# STM32F7.net
KiCad netlist of a schematic drawn in Altium Designer
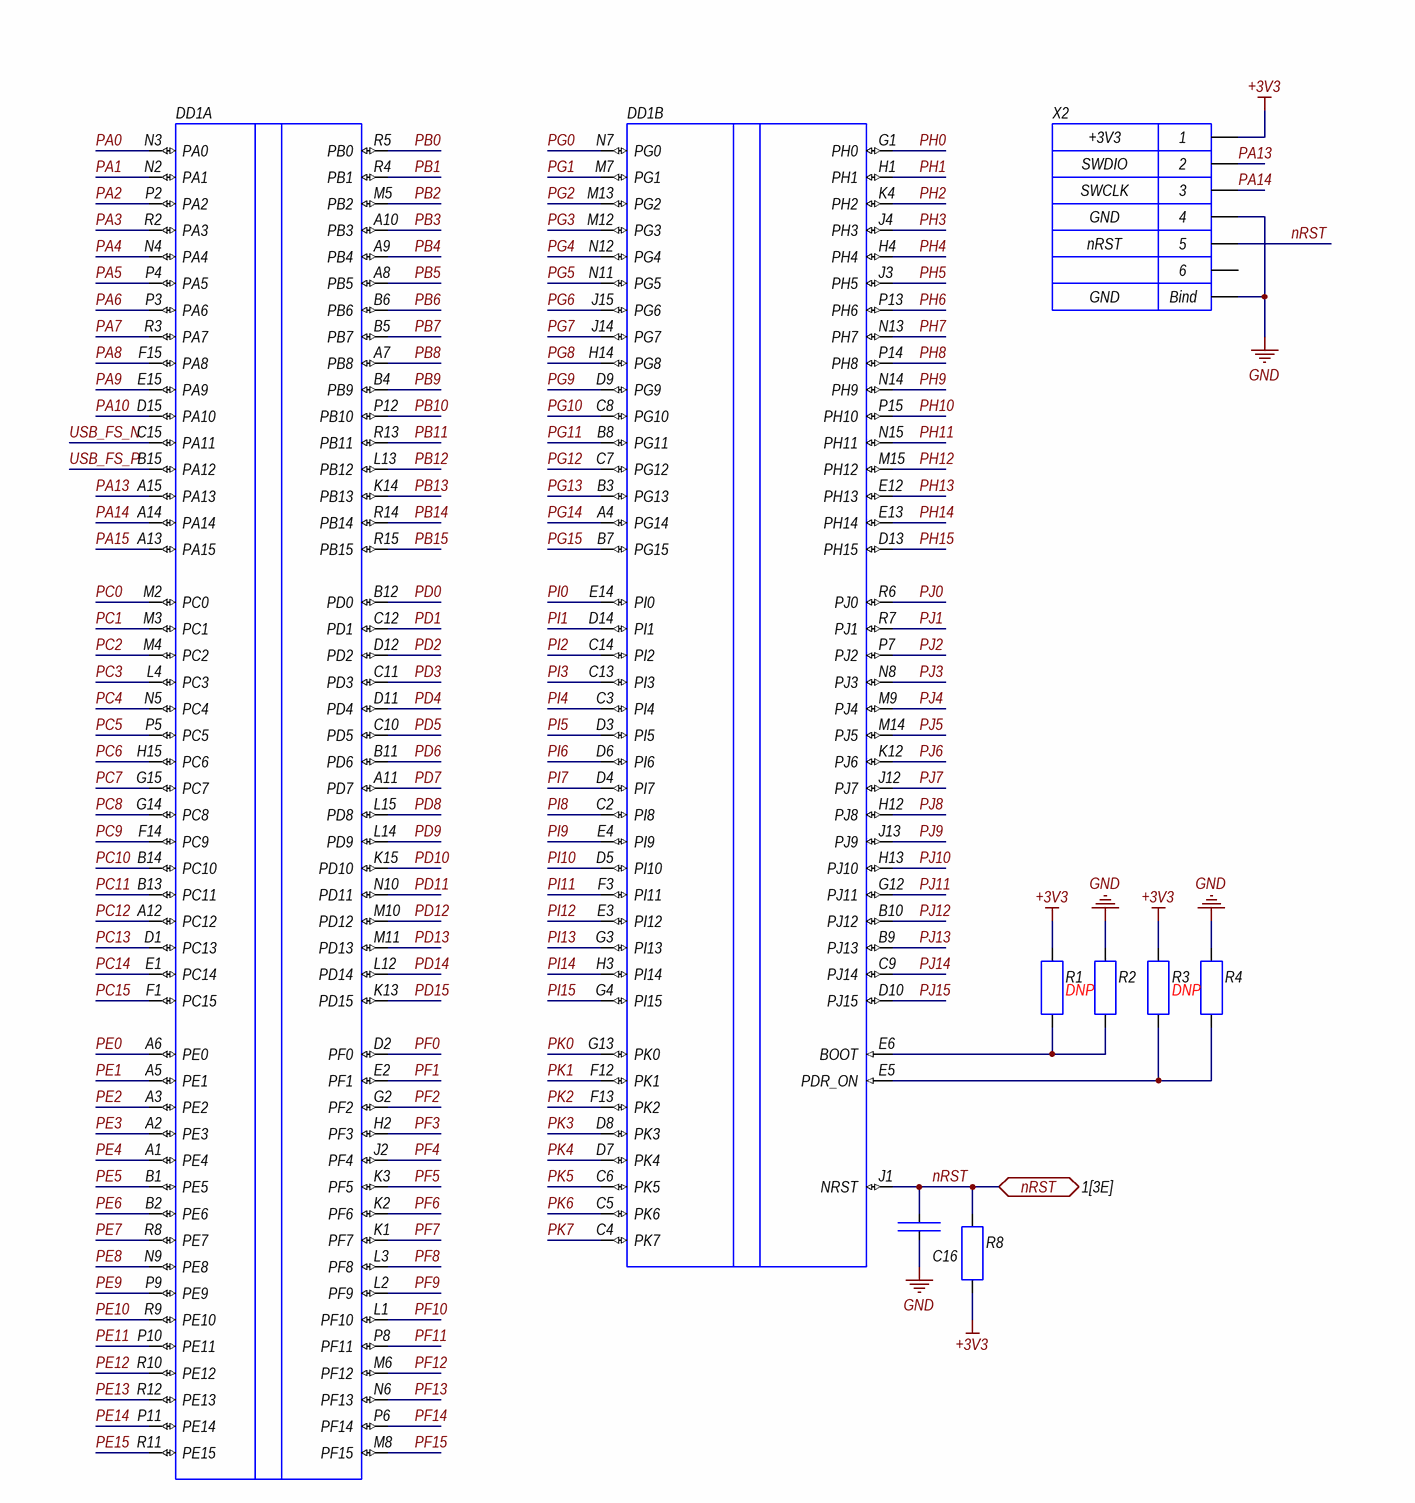
[diagram p0: STM32F7.SchDoc, top left]
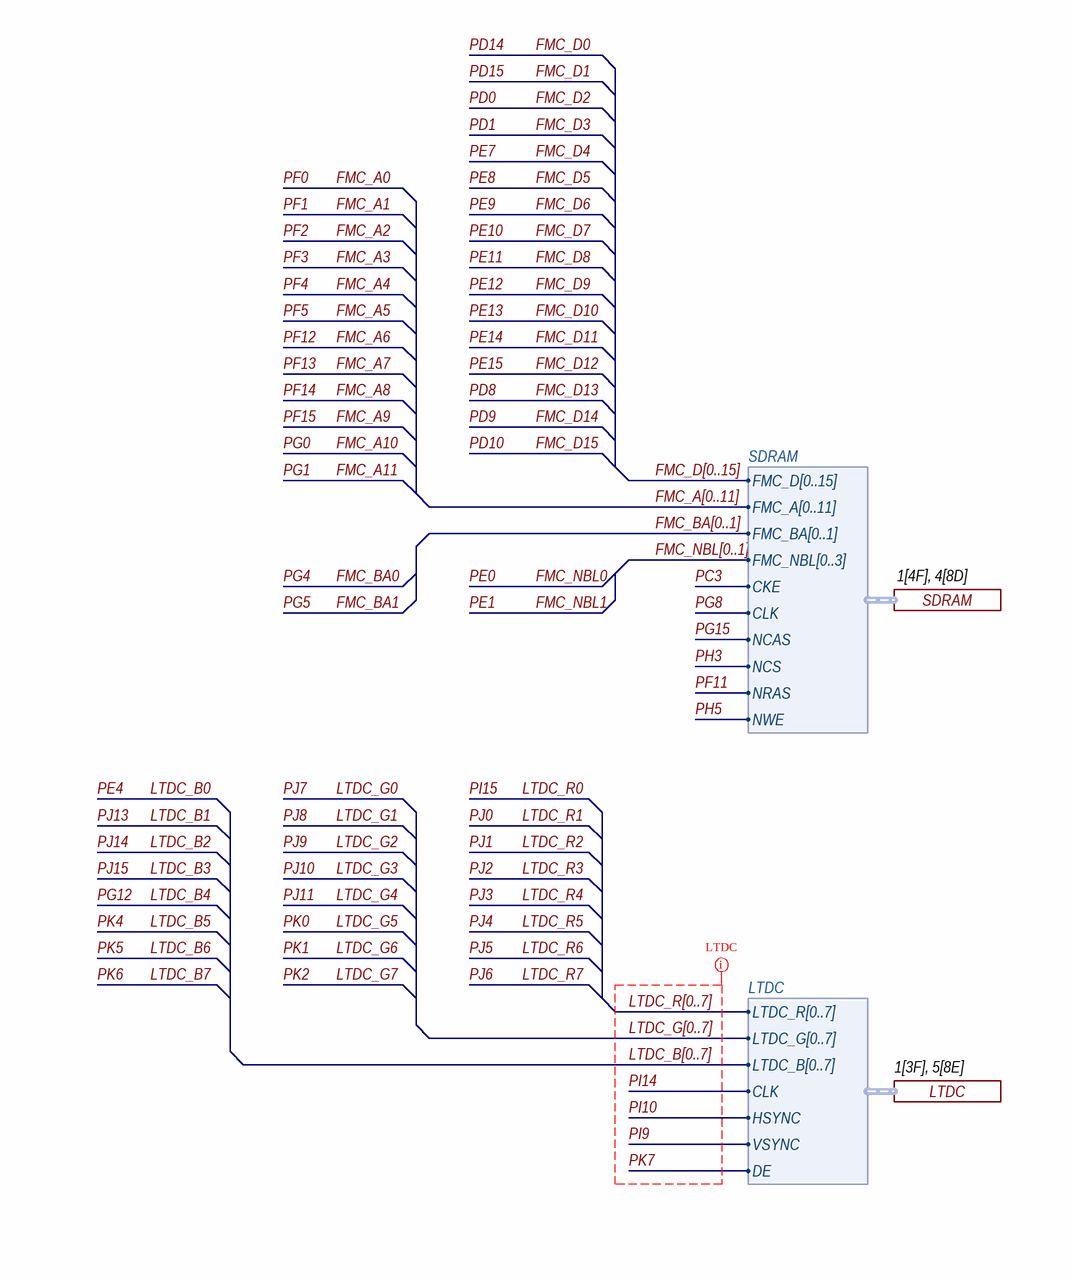
[diagram p1: STM32F7.SchDoc, top right]
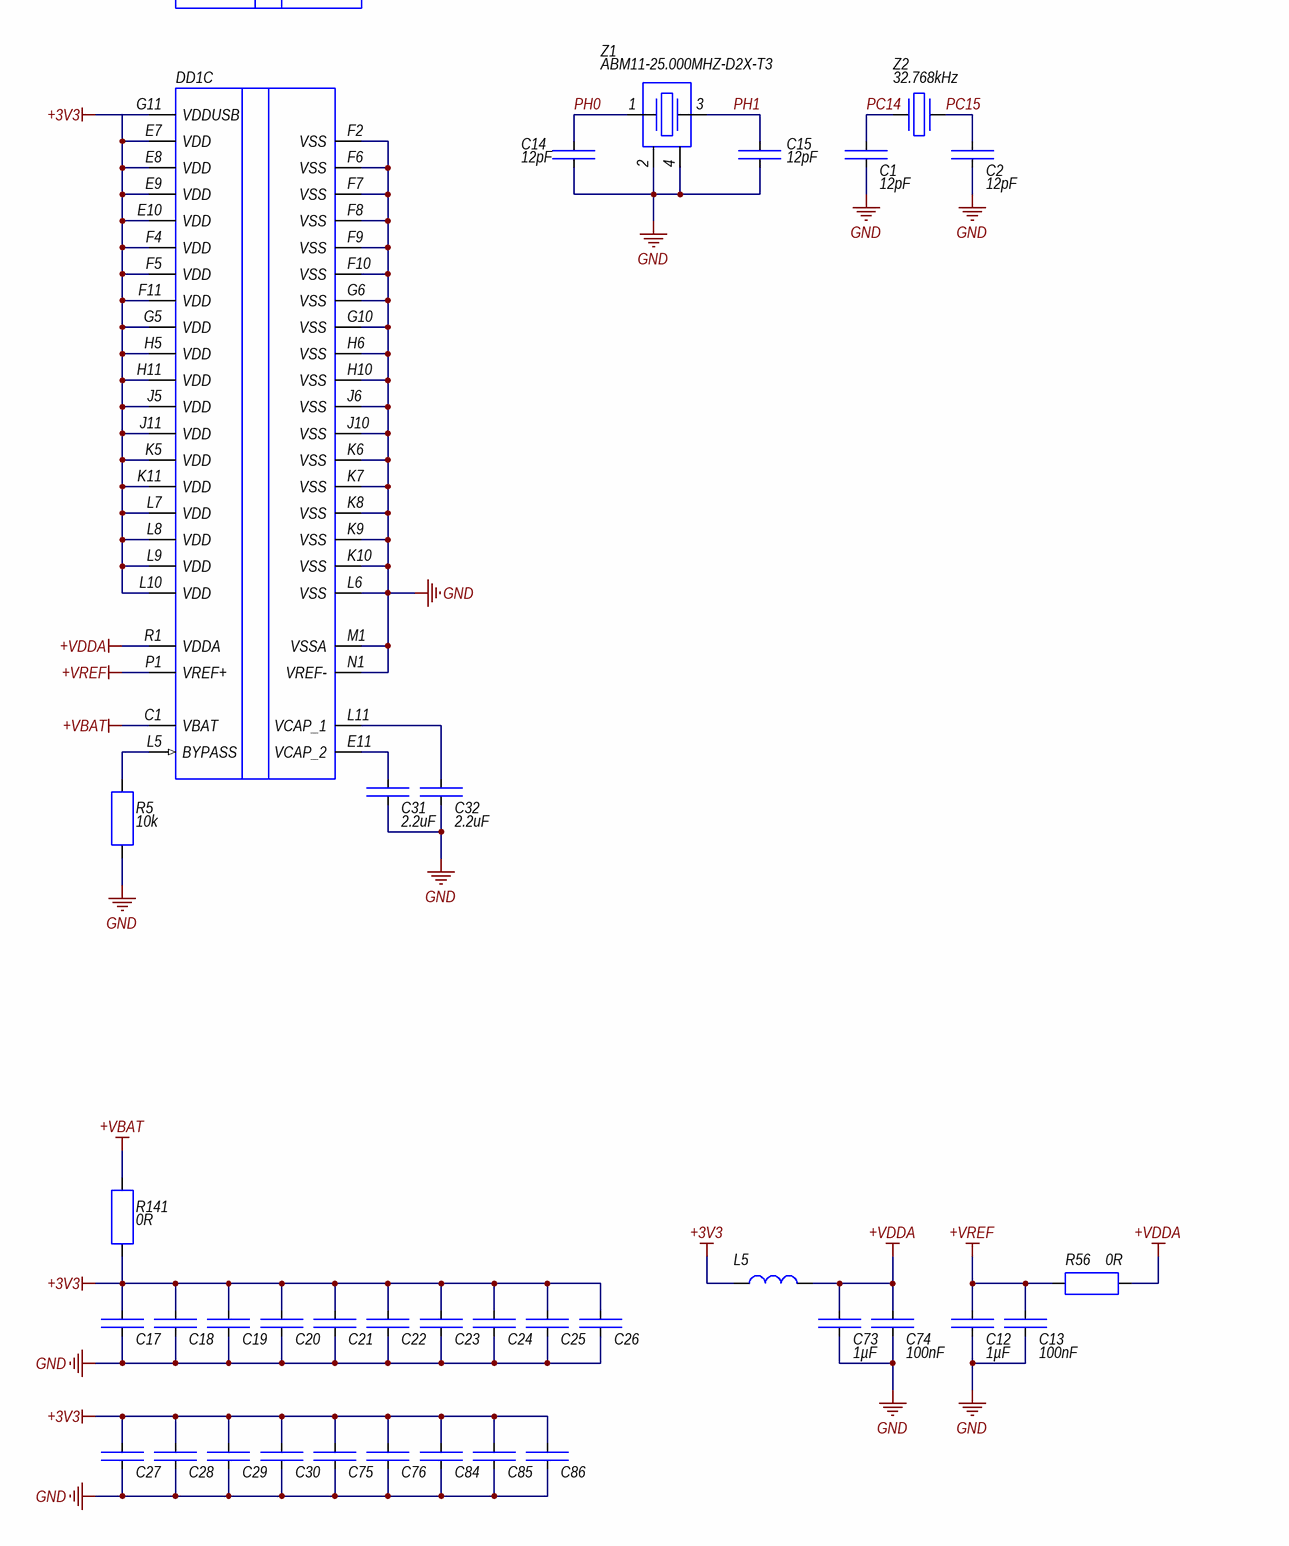
[diagram p2: STM32F7.SchDoc, bottom left]
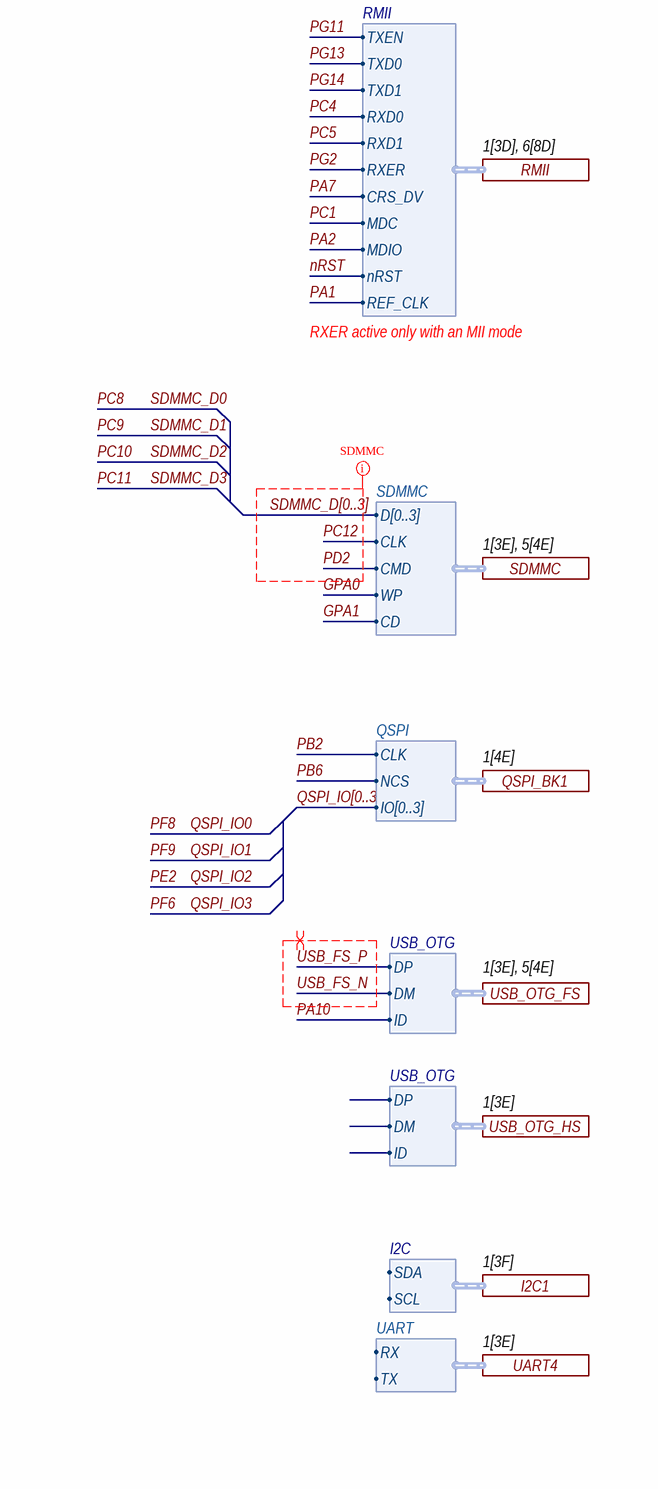
[diagram p3: STM32F7.SchDoc, bottom right]

(export (version "E")
  (design (tool "Eeschema 10.0.6"))
  (components
    (comp (ref "C1")
      (value "Конденсатор керам. ЧИП NP0, 5%, 0402, 12 пФ")
      (footprint "Capacitor 0402")
      (description "Cap Ceramic 12pF 50V C0G 2% Pad SMD 0402 125C Automotive T/R")
      (fields
        (field (name "CAPACITANCE") "12pF")
        (field (name "VOLTAGE") "50V")
        (field (name "MANUFACTURER") "Murata Manufacturing")
      )
      (libsource (lib "Eleps server") (part "Nonpolar Capacitor"))
    )
    (comp (ref "C2")
      (value "Конденсатор керам. ЧИП NP0, 5%, 0402, 12 пФ")
      (footprint "Capacitor 0402")
      (description "Cap Ceramic 12pF 50V C0G 2% Pad SMD 0402 125C Automotive T/R")
      (fields
        (field (name "CAPACITANCE") "12pF")
        (field (name "VOLTAGE") "50V")
        (field (name "MANUFACTURER") "Murata Manufacturing")
      )
      (libsource (lib "Eleps server") (part "Nonpolar Capacitor"))
    )
    (comp (ref "C12")
      (value "Конденсатор керам. ЧИП X5R, 10%, 0603, 1 мкФ")
      (footprint "Capacitor 0603")
      (description "Multilayer Ceramic Capacitors MLCC - SMD/SMT 0603 50V 1.0uF X5R 10%")
      (fields
        (field (name "CAPACITANCE") "1µF")
        (field (name "VOLTAGE") "50V")
        (field (name "MANUFACTURER") "Murata Electronics")
      )
      (libsource (lib "Eleps server") (part "Nonpolar Capacitor"))
    )
    (comp (ref "C13")
      (value "Конденсатор керам. ЧИП X7R, 10%, 0603, 0.1 мкФ")
      (footprint "Capacitor 0603")
      (fields
        (field (name "CAPACITANCE") "100nF")
        (field (name "VOLTAGE") "50V")
        (field (name "MANUFACTURER") "Yageo")
        (field (name "MANUFACTURER PART NUMBER") "CC0603KPX7R9BB104")
      )
      (libsource (lib "Eleps server") (part "Nonpolar Capacitor"))
    )
    (comp (ref "C14")
      (value "Конденсатор керам. ЧИП NP0, 5%, 0402, 12 пФ")
      (footprint "Capacitor 0402")
      (description "Cap Ceramic 12pF 50V C0G 2% Pad SMD 0402 125C Automotive T/R")
      (fields
        (field (name "CAPACITANCE") "12pF")
        (field (name "VOLTAGE") "50V")
        (field (name "MANUFACTURER") "Murata Manufacturing")
      )
      (libsource (lib "Eleps server") (part "Nonpolar Capacitor"))
    )
    (comp (ref "C15")
      (value "Конденсатор керам. ЧИП NP0, 5%, 0402, 12 пФ")
      (footprint "Capacitor 0402")
      (description "Cap Ceramic 12pF 50V C0G 2% Pad SMD 0402 125C Automotive T/R")
      (fields
        (field (name "CAPACITANCE") "12pF")
        (field (name "VOLTAGE") "50V")
        (field (name "MANUFACTURER") "Murata Manufacturing")
      )
      (libsource (lib "Eleps server") (part "Nonpolar Capacitor"))
    )
    (comp (ref "C16")
      (value "Конденсатор керам. ЧИП X5R, 10%, 0402, 0.1 мкФ")
      (footprint "Capacitor 0402")
      (description "Cap Ceramic 0.1uF 50V X5R 10% Pad SMD 0402 85C T/R")
      (fields (field (name "VOLTAGE") "50V") (field (name "MANUFACTURER") "Murata Manufacturing"))
      (libsource (lib "Eleps server") (part "Nonpolar Capacitor"))
    )
    (comp (ref "C17")
      (value "Конденсатор керам. ЧИП X5R, 10%, 0402, 0.1 мкФ")
      (footprint "Capacitor 0402")
      (description "Cap Ceramic 0.1uF 50V X5R 10% Pad SMD 0402 85C T/R")
      (fields (field (name "VOLTAGE") "50V") (field (name "MANUFACTURER") "Murata Manufacturing"))
      (libsource (lib "Eleps server") (part "Nonpolar Capacitor"))
    )
    (comp (ref "C18")
      (value "Конденсатор керам. ЧИП X5R, 10%, 0402, 0.1 мкФ")
      (footprint "Capacitor 0402")
      (description "Cap Ceramic 0.1uF 50V X5R 10% Pad SMD 0402 85C T/R")
      (fields (field (name "VOLTAGE") "50V") (field (name "MANUFACTURER") "Murata Manufacturing"))
      (libsource (lib "Eleps server") (part "Nonpolar Capacitor"))
    )
    (comp (ref "C19")
      (value "Конденсатор керам. ЧИП X5R, 10%, 0402, 0.1 мкФ")
      (footprint "Capacitor 0402")
      (description "Cap Ceramic 0.1uF 50V X5R 10% Pad SMD 0402 85C T/R")
      (fields (field (name "VOLTAGE") "50V") (field (name "MANUFACTURER") "Murata Manufacturing"))
      (libsource (lib "Eleps server") (part "Nonpolar Capacitor"))
    )
    (comp (ref "C20")
      (value "Конденсатор керам. ЧИП X5R, 10%, 0402, 0.1 мкФ")
      (footprint "Capacitor 0402")
      (description "Cap Ceramic 0.1uF 50V X5R 10% Pad SMD 0402 85C T/R")
      (fields (field (name "VOLTAGE") "50V") (field (name "MANUFACTURER") "Murata Manufacturing"))
      (libsource (lib "Eleps server") (part "Nonpolar Capacitor"))
    )
    (comp (ref "C21")
      (value "Конденсатор керам. ЧИП X5R, 10%, 0402, 0.1 мкФ")
      (footprint "Capacitor 0402")
      (description "Cap Ceramic 0.1uF 50V X5R 10% Pad SMD 0402 85C T/R")
      (fields (field (name "VOLTAGE") "50V") (field (name "MANUFACTURER") "Murata Manufacturing"))
      (libsource (lib "Eleps server") (part "Nonpolar Capacitor"))
    )
    (comp (ref "C22")
      (value "Конденсатор керам. ЧИП X5R, 10%, 0402, 0.1 мкФ")
      (footprint "Capacitor 0402")
      (description "Cap Ceramic 0.1uF 50V X5R 10% Pad SMD 0402 85C T/R")
      (fields (field (name "VOLTAGE") "50V") (field (name "MANUFACTURER") "Murata Manufacturing"))
      (libsource (lib "Eleps server") (part "Nonpolar Capacitor"))
    )
    (comp (ref "C23")
      (value "Конденсатор керам. ЧИП X5R, 10%, 0402, 0.1 мкФ")
      (footprint "Capacitor 0402")
      (description "Cap Ceramic 0.1uF 50V X5R 10% Pad SMD 0402 85C T/R")
      (fields (field (name "VOLTAGE") "50V") (field (name "MANUFACTURER") "Murata Manufacturing"))
      (libsource (lib "Eleps server") (part "Nonpolar Capacitor"))
    )
    (comp (ref "C24")
      (value "Конденсатор керам. ЧИП X5R, 10%, 0402, 0.1 мкФ")
      (footprint "Capacitor 0402")
      (description "Cap Ceramic 0.1uF 50V X5R 10% Pad SMD 0402 85C T/R")
      (fields (field (name "VOLTAGE") "50V") (field (name "MANUFACTURER") "Murata Manufacturing"))
      (libsource (lib "Eleps server") (part "Nonpolar Capacitor"))
    )
    (comp (ref "C25")
      (value "Конденсатор керам. ЧИП X5R, 10%, 0402, 0.1 мкФ")
      (footprint "Capacitor 0402")
      (description "Cap Ceramic 0.1uF 50V X5R 10% Pad SMD 0402 85C T/R")
      (fields (field (name "VOLTAGE") "50V") (field (name "MANUFACTURER") "Murata Manufacturing"))
      (libsource (lib "Eleps server") (part "Nonpolar Capacitor"))
    )
    (comp (ref "C26")
      (value "Конденсатор керам. ЧИП X5R, 10%, 0402, 0.1 мкФ")
      (footprint "Capacitor 0402")
      (description "Cap Ceramic 0.1uF 50V X5R 10% Pad SMD 0402 85C T/R")
      (fields (field (name "VOLTAGE") "50V") (field (name "MANUFACTURER") "Murata Manufacturing"))
      (libsource (lib "Eleps server") (part "Nonpolar Capacitor"))
    )
    (comp (ref "C27")
      (value "Конденсатор керам. ЧИП X5R, 10%, 0402, 0.1 мкФ")
      (footprint "Capacitor 0402")
      (description "Cap Ceramic 0.1uF 50V X5R 10% Pad SMD 0402 85C T/R")
      (fields (field (name "VOLTAGE") "50V") (field (name "MANUFACTURER") "Murata Manufacturing"))
      (libsource (lib "Eleps server") (part "Nonpolar Capacitor"))
    )
    (comp (ref "C28")
      (value "Конденсатор керам. ЧИП X5R, 10%, 0402, 0.1 мкФ")
      (footprint "Capacitor 0402")
      (description "Cap Ceramic 0.1uF 50V X5R 10% Pad SMD 0402 85C T/R")
      (fields (field (name "VOLTAGE") "50V") (field (name "MANUFACTURER") "Murata Manufacturing"))
      (libsource (lib "Eleps server") (part "Nonpolar Capacitor"))
    )
    (comp (ref "C29")
      (value "Конденсатор керам. ЧИП X5R, 10%, 0402, 0.1 мкФ")
      (footprint "Capacitor 0402")
      (description "Cap Ceramic 0.1uF 50V X5R 10% Pad SMD 0402 85C T/R")
      (fields (field (name "VOLTAGE") "50V") (field (name "MANUFACTURER") "Murata Manufacturing"))
      (libsource (lib "Eleps server") (part "Nonpolar Capacitor"))
    )
    (comp (ref "C30")
      (value "Конденсатор керам. ЧИП X5R, 10%, 0402, 0.1 мкФ")
      (footprint "Capacitor 0402")
      (description "Cap Ceramic 0.1uF 50V X5R 10% Pad SMD 0402 85C T/R")
      (fields (field (name "VOLTAGE") "50V") (field (name "MANUFACTURER") "Murata Manufacturing"))
      (libsource (lib "Eleps server") (part "Nonpolar Capacitor"))
    )
    (comp (ref "C31")
      (value "NCap")
      (footprint "SMD_1206")
      (fields (field (name "CAPACITANCE") "2.2uF") (field (name "PART NUMBER") "Capacitor_1206"))
      (libsource (lib "PhLib") (part "NCap"))
    )
    (comp (ref "C32")
      (value "NCap")
      (footprint "SMD_1206")
      (fields (field (name "CAPACITANCE") "2.2uF") (field (name "PART NUMBER") "Capacitor_1206"))
      (libsource (lib "PhLib") (part "NCap"))
    )
    (comp (ref "C73")
      (value "Конденсатор керам. ЧИП X5R, 10%, 0603, 1 мкФ")
      (footprint "Capacitor 0603")
      (description "Multilayer Ceramic Capacitors MLCC - SMD/SMT 0603 50V 1.0uF X5R 10%")
      (fields
        (field (name "CAPACITANCE") "1µF")
        (field (name "VOLTAGE") "50V")
        (field (name "MANUFACTURER") "Murata Electronics")
      )
      (libsource (lib "Eleps server") (part "Nonpolar Capacitor"))
    )
    (comp (ref "C74")
      (value "Конденсатор керам. ЧИП X7R, 10%, 0603, 0.1 мкФ")
      (footprint "Capacitor 0603")
      (fields
        (field (name "CAPACITANCE") "100nF")
        (field (name "VOLTAGE") "50V")
        (field (name "MANUFACTURER") "Yageo")
        (field (name "MANUFACTURER PART NUMBER") "CC0603KPX7R9BB104")
      )
      (libsource (lib "Eleps server") (part "Nonpolar Capacitor"))
    )
    (comp (ref "C75")
      (value "Конденсатор керам. ЧИП X5R, 10%, 0402, 0.1 мкФ")
      (footprint "Capacitor 0402")
      (description "Cap Ceramic 0.1uF 50V X5R 10% Pad SMD 0402 85C T/R")
      (fields (field (name "VOLTAGE") "50V") (field (name "MANUFACTURER") "Murata Manufacturing"))
      (libsource (lib "Eleps server") (part "Nonpolar Capacitor"))
    )
    (comp (ref "C76")
      (value "Конденсатор керам. ЧИП X5R, 10%, 0402, 0.1 мкФ")
      (footprint "Capacitor 0402")
      (description "Cap Ceramic 0.1uF 50V X5R 10% Pad SMD 0402 85C T/R")
      (fields (field (name "VOLTAGE") "50V") (field (name "MANUFACTURER") "Murata Manufacturing"))
      (libsource (lib "Eleps server") (part "Nonpolar Capacitor"))
    )
    (comp (ref "C84")
      (value "Конденсатор керам. ЧИП X5R, 10%, 0402, 0.1 мкФ")
      (footprint "Capacitor 0402")
      (description "Cap Ceramic 0.1uF 50V X5R 10% Pad SMD 0402 85C T/R")
      (fields (field (name "VOLTAGE") "50V") (field (name "MANUFACTURER") "Murata Manufacturing"))
      (libsource (lib "Eleps server") (part "Nonpolar Capacitor"))
    )
    (comp (ref "C85")
      (value "Конденсатор керам. ЧИП X5R, 10%, 0402, 0.1 мкФ")
      (footprint "Capacitor 0402")
      (description "Cap Ceramic 0.1uF 50V X5R 10% Pad SMD 0402 85C T/R")
      (fields (field (name "VOLTAGE") "50V") (field (name "MANUFACTURER") "Murata Manufacturing"))
      (libsource (lib "Eleps server") (part "Nonpolar Capacitor"))
    )
    (comp (ref "C86")
      (value "Конденсатор керам. ЧИП X5R, 10%, 0402, 0.1 мкФ")
      (footprint "Capacitor 0402")
      (description "Cap Ceramic 0.1uF 50V X5R 10% Pad SMD 0402 85C T/R")
      (fields (field (name "VOLTAGE") "50V") (field (name "MANUFACTURER") "Murata Manufacturing"))
      (libsource (lib "Eleps server") (part "Nonpolar Capacitor"))
    )
    (comp (ref "DD1")
      (value "Микросхема STM32F746NGH6")
      (footprint "STM-TFBGA216")
      (fields (field (name "PART NUMBER") "STM32F746NGH6") (field (name "MANUFACTURER") "STMicroelectronics"))
      (libsource (lib "PhLib") (part "STM32F746NGH6"))
    )
    (comp (ref "L5")
      (value "Дроссель BLM18HE152SN1D")
      (footprint "BLM18HE152SN1D")
      (description "Ferrite bead")
      (fields
        (field (name "MANUFACTURER") "Murata Electronics")
        (field (name "MANUFACTURER PART NUMBER") "BLM18HE152SN1D")
      )
      (libsource (lib "Eleps server") (part "Inductor"))
    )
    (comp (ref "R1")
      (value "~")
      (footprint "SMD_0402")
      (fields (field (name "PART NUMBER") "Resistor_0402"))
      (libsource (lib "PhLib") (part "Resistor"))
    )
    (comp (ref "R2")
      (value "~")
      (footprint "SMD_0402")
      (fields (field (name "PART NUMBER") "Resistor_0402"))
      (libsource (lib "PhLib") (part "Resistor"))
    )
    (comp (ref "R3")
      (value "~")
      (footprint "SMD_0402")
      (fields (field (name "PART NUMBER") "Resistor_0402"))
      (libsource (lib "PhLib") (part "Resistor"))
    )
    (comp (ref "R4")
      (value "~")
      (footprint "SMD_0402")
      (fields (field (name "PART NUMBER") "Resistor_0402"))
      (libsource (lib "PhLib") (part "Resistor"))
    )
    (comp (ref "R5")
      (value "~")
      (footprint "SMD_0402")
      (fields (field (name "PART NUMBER") "Resistor_0402") (field (name "RESISTANCE") "10k"))
      (libsource (lib "PhLib") (part "Resistor"))
    )
    (comp (ref "R8")
      (value "~")
      (footprint "SMD_0402")
      (fields (field (name "PART NUMBER") "Resistor_0402"))
      (libsource (lib "PhLib") (part "Resistor"))
    )
    (comp (ref "R56")
      (value "Resistor")
      (footprint "SMD_0402")
      (fields (field (name "DEVICE") "0R") (field (name "PART NUMBER") "Resistor_0402"))
      (libsource (lib "") (part "Resistor_1"))
    )
    (comp (ref "R141")
      (value "~")
      (footprint "SMD_0402")
      (fields (field (name "PART NUMBER") "Resistor_0402") (field (name "RESISTANCE") "0R"))
      (libsource (lib "PhLib") (part "Resistor"))
    )
    (comp (ref "X2")
      (value "Вилка DF13C-6P-1.25V(50)")
      (footprint "DF13C-6P-1.25V(50)")
      (fields (field (name "MANUFACTURER PART NUMBER") "DF13C-6P-1.25V(50)"))
      (libsource (lib "Eleps server") (part "6-connector-bind"))
    )
    (comp (ref "Z1")
      (value "Резонатор ABM11-25.000MHZ-D2X-T3")
      (footprint "ABM11-MFG")
      (description "Crystal 25MHz ±20ppm (Tol) ±20ppm (Stability) 10pF FUND 100Ohm 4-Pin Ultra Mini-CSMD T/R")
      (fields
        (field (name "MANUFACTURER") "Abracon")
        (field (name "MANUFACTURER PART NUMBER") "ABM11-25.000MHZ-D2X-T3")
      )
      (libsource (lib "Altium Vault") (part "KX-9A"))
    )
    (comp (ref "Z2")
      (value "Резонатор NX3215SA 32.768 кГц")
      (footprint "FP-NX3215SA-MFG")
      (description "32.768kHz")
      (fields
        (field (name "MANUFACTURER") "NDK")
        (field (name "MANUFACTURER PART NUMBER") "NX3215SA-32.768K-STD-MUA-8")
        (field (name "DEVICE") "32.768kHz")
      )
      (libsource (lib "Eleps server") (part "Resonator"))
    )
  )
  (nets
    (net (code "9") (name "+3V3") (class "Default")
      (node (ref "C17") (pin "1") (pinfunction "1_1") (pintype "passive"))
      (node (ref "C18") (pin "1") (pinfunction "1_1") (pintype "passive"))
      (node (ref "C19") (pin "1") (pinfunction "1_1") (pintype "passive"))
      (node (ref "C20") (pin "1") (pinfunction "1_1") (pintype "passive"))
      (node (ref "C21") (pin "1") (pinfunction "1_1") (pintype "passive"))
      (node (ref "C22") (pin "1") (pinfunction "1_1") (pintype "passive"))
      (node (ref "C23") (pin "1") (pinfunction "1_1") (pintype "passive"))
      (node (ref "C24") (pin "1") (pinfunction "1_1") (pintype "passive"))
      (node (ref "C25") (pin "1") (pinfunction "1_1") (pintype "passive"))
      (node (ref "C26") (pin "1") (pinfunction "1_1") (pintype "passive"))
      (node (ref "C27") (pin "1") (pinfunction "1_1") (pintype "passive"))
      (node (ref "C28") (pin "1") (pinfunction "1_1") (pintype "passive"))
      (node (ref "C29") (pin "1") (pinfunction "1_1") (pintype "passive"))
      (node (ref "C30") (pin "1") (pinfunction "1_1") (pintype "passive"))
      (node (ref "C75") (pin "1") (pinfunction "1_1") (pintype "passive"))
      (node (ref "C76") (pin "1") (pinfunction "1_1") (pintype "passive"))
      (node (ref "C84") (pin "1") (pinfunction "1_1") (pintype "passive"))
      (node (ref "C85") (pin "1") (pinfunction "1_1") (pintype "passive"))
      (node (ref "C86") (pin "1") (pinfunction "1_1") (pintype "passive"))
      (node (ref "DD1") (pin "E10") (pinfunction "VDD_E10") (pintype "power_in"))
      (node (ref "DD1") (pin "E7") (pinfunction "VDD_E7") (pintype "power_in"))
      (node (ref "DD1") (pin "E8") (pinfunction "VDD_E8") (pintype "power_in"))
      (node (ref "DD1") (pin "E9") (pinfunction "VDD_E9") (pintype "power_in"))
      (node (ref "DD1") (pin "F11") (pinfunction "VDD_F11") (pintype "power_in"))
      (node (ref "DD1") (pin "F4") (pinfunction "VDD_F4") (pintype "power_in"))
      (node (ref "DD1") (pin "F5") (pinfunction "VDD_F5") (pintype "power_in"))
      (node (ref "DD1") (pin "G11") (pinfunction "VDDUSB_G11") (pintype "power_in"))
      (node (ref "DD1") (pin "G5") (pinfunction "VDD_G5") (pintype "power_in"))
      (node (ref "DD1") (pin "H11") (pinfunction "VDD_H11") (pintype "power_in"))
      (node (ref "DD1") (pin "H5") (pinfunction "VDD_H5") (pintype "power_in"))
      (node (ref "DD1") (pin "J11") (pinfunction "VDD_J11") (pintype "power_in"))
      (node (ref "DD1") (pin "J5") (pinfunction "VDD_J5") (pintype "power_in"))
      (node (ref "DD1") (pin "K11") (pinfunction "VDD_K11") (pintype "power_in"))
      (node (ref "DD1") (pin "K5") (pinfunction "VDD_K5") (pintype "power_in"))
      (node (ref "DD1") (pin "L10") (pinfunction "VDD_L10") (pintype "power_in"))
      (node (ref "DD1") (pin "L7") (pinfunction "VDD_L7") (pintype "power_in"))
      (node (ref "DD1") (pin "L8") (pinfunction "VDD_L8") (pintype "power_in"))
      (node (ref "DD1") (pin "L9") (pinfunction "VDD_L9") (pintype "power_in"))
      (node (ref "L5") (pin "1") (pinfunction "1_1") (pintype "passive"))
      (node (ref "R1") (pin "2") (pinfunction "2_2") (pintype "passive"))
      (node (ref "R141") (pin "1") (pinfunction "1_1") (pintype "passive"))
      (node (ref "R3") (pin "2") (pinfunction "2_2") (pintype "passive"))
      (node (ref "R8") (pin "1") (pinfunction "1_1") (pintype "passive"))
      (node (ref "X2") (pin "1") (pinfunction "1_1") (pintype "passive"))
    )
    (net (code "10") (name "+VBAT") (class "Default")
      (node (ref "DD1") (pin "C1") (pinfunction "VBAT_C1") (pintype "power_in"))
      (node (ref "R141") (pin "2") (pinfunction "2_2") (pintype "passive"))
    )
    (net (code "11") (name "+VDDA") (class "Default")
      (node (ref "C73") (pin "1") (pinfunction "1_1") (pintype "passive"))
      (node (ref "C74") (pin "1") (pinfunction "1_1") (pintype "passive"))
      (node (ref "DD1") (pin "R1") (pinfunction "VDDA_R1") (pintype "power_in"))
      (node (ref "L5") (pin "2") (pinfunction "2_2") (pintype "passive"))
      (node (ref "R56") (pin "2") (pinfunction "2_2") (pintype "passive"))
    )
    (net (code "12") (name "+VREF") (class "Default")
      (node (ref "C12") (pin "1") (pinfunction "1_1") (pintype "passive"))
      (node (ref "C13") (pin "1") (pinfunction "1_1") (pintype "passive"))
      (node (ref "DD1") (pin "P1") (pinfunction "VREF+_P1") (pintype "power_in"))
      (node (ref "R56") (pin "1") (pinfunction "1_1") (pintype "passive"))
    )
    (net (code "13") (name "/FMC_A0") (class "Default")
      (node (ref "DD1") (pin "D2") (pinfunction "PF0_D2") (pintype "bidirectional"))
    )
    (net (code "14") (name "/FMC_A1") (class "Default")
      (node (ref "DD1") (pin "E2") (pinfunction "PF1_E2") (pintype "bidirectional"))
    )
    (net (code "15") (name "/FMC_A2") (class "Default")
      (node (ref "DD1") (pin "G2") (pinfunction "PF2_G2") (pintype "bidirectional"))
    )
    (net (code "16") (name "/FMC_A3") (class "Default")
      (node (ref "DD1") (pin "H2") (pinfunction "PF3_H2") (pintype "bidirectional"))
    )
    (net (code "17") (name "/FMC_A4") (class "Default")
      (node (ref "DD1") (pin "J2") (pinfunction "PF4_J2") (pintype "bidirectional"))
    )
    (net (code "18") (name "/FMC_A5") (class "Default")
      (node (ref "DD1") (pin "K3") (pinfunction "PF5_K3") (pintype "bidirectional"))
    )
    (net (code "19") (name "/FMC_A6") (class "Default")
      (node (ref "DD1") (pin "M6") (pinfunction "PF12_M6") (pintype "bidirectional"))
    )
    (net (code "20") (name "/FMC_A7") (class "Default")
      (node (ref "DD1") (pin "N6") (pinfunction "PF13_N6") (pintype "bidirectional"))
    )
    (net (code "21") (name "/FMC_A8") (class "Default")
      (node (ref "DD1") (pin "P6") (pinfunction "PF14_P6") (pintype "bidirectional"))
    )
    (net (code "22") (name "/FMC_A9") (class "Default")
      (node (ref "DD1") (pin "M8") (pinfunction "PF15_M8") (pintype "bidirectional"))
    )
    (net (code "23") (name "/FMC_A10") (class "Default")
      (node (ref "DD1") (pin "N7") (pinfunction "PG0_N7") (pintype "bidirectional"))
    )
    (net (code "24") (name "/FMC_A11") (class "Default")
      (node (ref "DD1") (pin "M7") (pinfunction "PG1_M7") (pintype "bidirectional"))
    )
    (net (code "26") (name "/FMC_BA0") (class "Default")
      (node (ref "DD1") (pin "N12") (pinfunction "PG4_N12") (pintype "bidirectional"))
    )
    (net (code "27") (name "/FMC_BA1") (class "Default")
      (node (ref "DD1") (pin "N11") (pinfunction "PG5_N11") (pintype "bidirectional"))
    )
    (net (code "29") (name "/FMC_D0") (class "Default")
      (node (ref "DD1") (pin "L12") (pinfunction "PD14_L12") (pintype "bidirectional"))
    )
    (net (code "30") (name "/FMC_D1") (class "Default")
      (node (ref "DD1") (pin "K13") (pinfunction "PD15_K13") (pintype "bidirectional"))
    )
    (net (code "31") (name "/FMC_D2") (class "Default")
      (node (ref "DD1") (pin "B12") (pinfunction "PD0_B12") (pintype "bidirectional"))
    )
    (net (code "32") (name "/FMC_D3") (class "Default")
      (node (ref "DD1") (pin "C12") (pinfunction "PD1_C12") (pintype "bidirectional"))
    )
    (net (code "33") (name "/FMC_D4") (class "Default")
      (node (ref "DD1") (pin "R8") (pinfunction "PE7_R8") (pintype "bidirectional"))
    )
    (net (code "34") (name "/FMC_D5") (class "Default")
      (node (ref "DD1") (pin "N9") (pinfunction "PE8_N9") (pintype "bidirectional"))
    )
    (net (code "35") (name "/FMC_D6") (class "Default")
      (node (ref "DD1") (pin "P9") (pinfunction "PE9_P9") (pintype "bidirectional"))
    )
    (net (code "36") (name "/FMC_D7") (class "Default")
      (node (ref "DD1") (pin "R9") (pinfunction "PE10_R9") (pintype "bidirectional"))
    )
    (net (code "37") (name "/FMC_D8") (class "Default")
      (node (ref "DD1") (pin "P10") (pinfunction "PE11_P10") (pintype "bidirectional"))
    )
    (net (code "38") (name "/FMC_D9") (class "Default")
      (node (ref "DD1") (pin "R10") (pinfunction "PE12_R10") (pintype "bidirectional"))
    )
    (net (code "39") (name "/FMC_D10") (class "Default")
      (node (ref "DD1") (pin "R12") (pinfunction "PE13_R12") (pintype "bidirectional"))
    )
    (net (code "40") (name "/FMC_D11") (class "Default")
      (node (ref "DD1") (pin "P11") (pinfunction "PE14_P11") (pintype "bidirectional"))
    )
    (net (code "41") (name "/FMC_D12") (class "Default")
      (node (ref "DD1") (pin "R11") (pinfunction "PE15_R11") (pintype "bidirectional"))
    )
    (net (code "42") (name "/FMC_D13") (class "Default")
      (node (ref "DD1") (pin "L15") (pinfunction "PD8_L15") (pintype "bidirectional"))
    )
    (net (code "43") (name "/FMC_D14") (class "Default")
      (node (ref "DD1") (pin "L14") (pinfunction "PD9_L14") (pintype "bidirectional"))
    )
    (net (code "44") (name "/FMC_D15") (class "Default")
      (node (ref "DD1") (pin "K15") (pinfunction "PD10_K15") (pintype "bidirectional"))
    )
    (net (code "46") (name "/FMC_NBL0") (class "Default")
      (node (ref "DD1") (pin "A6") (pinfunction "PE0_A6") (pintype "bidirectional"))
    )
    (net (code "47") (name "/FMC_NBL1") (class "Default")
      (node (ref "DD1") (pin "A5") (pinfunction "PE1_A5") (pintype "bidirectional"))
    )
    (net (code "51") (name "/LTDC_B0") (class "Default")
      (node (ref "DD1") (pin "A1") (pinfunction "PE4_A1") (pintype "bidirectional"))
    )
    (net (code "52") (name "/LTDC_B1") (class "Default")
      (node (ref "DD1") (pin "B9") (pinfunction "PJ13_B9") (pintype "bidirectional"))
    )
    (net (code "53") (name "/LTDC_B2") (class "Default")
      (node (ref "DD1") (pin "C9") (pinfunction "PJ14_C9") (pintype "bidirectional"))
    )
    (net (code "54") (name "/LTDC_B3") (class "Default")
      (node (ref "DD1") (pin "D10") (pinfunction "PJ15_D10") (pintype "bidirectional"))
    )
    (net (code "55") (name "/LTDC_B4") (class "Default")
      (node (ref "DD1") (pin "C7") (pinfunction "PG12_C7") (pintype "bidirectional"))
    )
    (net (code "56") (name "/LTDC_B5") (class "Default")
      (node (ref "DD1") (pin "D7") (pinfunction "PK4_D7") (pintype "bidirectional"))
    )
    (net (code "57") (name "/LTDC_B6") (class "Default")
      (node (ref "DD1") (pin "C6") (pinfunction "PK5_C6") (pintype "bidirectional"))
    )
    (net (code "58") (name "/LTDC_B7") (class "Default")
      (node (ref "DD1") (pin "C5") (pinfunction "PK6_C5") (pintype "bidirectional"))
    )
    (net (code "60") (name "/LTDC_G0") (class "Default")
      (node (ref "DD1") (pin "J12") (pinfunction "PJ7_J12") (pintype "bidirectional"))
    )
    (net (code "61") (name "/LTDC_G1") (class "Default")
      (node (ref "DD1") (pin "H12") (pinfunction "PJ8_H12") (pintype "bidirectional"))
    )
    (net (code "62") (name "/LTDC_G2") (class "Default")
      (node (ref "DD1") (pin "J13") (pinfunction "PJ9_J13") (pintype "bidirectional"))
    )
    (net (code "63") (name "/LTDC_G3") (class "Default")
      (node (ref "DD1") (pin "H13") (pinfunction "PJ10_H13") (pintype "bidirectional"))
    )
    (net (code "64") (name "/LTDC_G4") (class "Default")
      (node (ref "DD1") (pin "G12") (pinfunction "PJ11_G12") (pintype "bidirectional"))
    )
    (net (code "65") (name "/LTDC_G5") (class "Default")
      (node (ref "DD1") (pin "G13") (pinfunction "PK0_G13") (pintype "bidirectional"))
    )
    (net (code "66") (name "/LTDC_G6") (class "Default")
      (node (ref "DD1") (pin "F12") (pinfunction "PK1_F12") (pintype "bidirectional"))
    )
    (net (code "67") (name "/LTDC_G7") (class "Default")
      (node (ref "DD1") (pin "F13") (pinfunction "PK2_F13") (pintype "bidirectional"))
    )
    (net (code "69") (name "/LTDC_R0") (class "Default")
      (node (ref "DD1") (pin "G4") (pinfunction "PI15_G4") (pintype "bidirectional"))
    )
    (net (code "70") (name "/LTDC_R1") (class "Default")
      (node (ref "DD1") (pin "R6") (pinfunction "PJ0_R6") (pintype "bidirectional"))
    )
    (net (code "71") (name "/LTDC_R2") (class "Default")
      (node (ref "DD1") (pin "R7") (pinfunction "PJ1_R7") (pintype "bidirectional"))
    )
    (net (code "72") (name "/LTDC_R3") (class "Default")
      (node (ref "DD1") (pin "P7") (pinfunction "PJ2_P7") (pintype "bidirectional"))
    )
    (net (code "73") (name "/LTDC_R4") (class "Default")
      (node (ref "DD1") (pin "N8") (pinfunction "PJ3_N8") (pintype "bidirectional"))
    )
    (net (code "74") (name "/LTDC_R5") (class "Default")
      (node (ref "DD1") (pin "M9") (pinfunction "PJ4_M9") (pintype "bidirectional"))
    )
    (net (code "75") (name "/LTDC_R6") (class "Default")
      (node (ref "DD1") (pin "M14") (pinfunction "PJ5_M14") (pintype "bidirectional"))
    )
    (net (code "76") (name "/LTDC_R7") (class "Default")
      (node (ref "DD1") (pin "K12") (pinfunction "PJ6_K12") (pintype "bidirectional"))
    )
    (net (code "78") (name "/PA0") (class "Default")
      (node (ref "DD1") (pin "N3") (pinfunction "PA0_N3") (pintype "bidirectional"))
    )
    (net (code "79") (name "/PA1") (class "Default")
      (node (ref "DD1") (pin "N2") (pinfunction "PA1_N2") (pintype "bidirectional"))
    )
    (net (code "80") (name "/PA2") (class "Default")
      (node (ref "DD1") (pin "P2") (pinfunction "PA2_P2") (pintype "bidirectional"))
    )
    (net (code "81") (name "/PA3") (class "Default")
      (node (ref "DD1") (pin "R2") (pinfunction "PA3_R2") (pintype "bidirectional"))
    )
    (net (code "82") (name "/PA4") (class "Default")
      (node (ref "DD1") (pin "N4") (pinfunction "PA4_N4") (pintype "bidirectional"))
    )
    (net (code "83") (name "/PA5") (class "Default")
      (node (ref "DD1") (pin "P4") (pinfunction "PA5_P4") (pintype "bidirectional"))
    )
    (net (code "84") (name "/PA6") (class "Default")
      (node (ref "DD1") (pin "P3") (pinfunction "PA6_P3") (pintype "bidirectional"))
    )
    (net (code "85") (name "/PA7") (class "Default")
      (node (ref "DD1") (pin "R3") (pinfunction "PA7_R3") (pintype "bidirectional"))
    )
    (net (code "86") (name "/PA8") (class "Default")
      (node (ref "DD1") (pin "F15") (pinfunction "PA8_F15") (pintype "bidirectional"))
    )
    (net (code "87") (name "/PA9") (class "Default")
      (node (ref "DD1") (pin "E15") (pinfunction "PA9_E15") (pintype "bidirectional"))
    )
    (net (code "88") (name "/PA10") (class "Default")
      (node (ref "DD1") (pin "D15") (pinfunction "PA10_D15") (pintype "bidirectional"))
    )
    (net (code "89") (name "/PA13") (class "Default")
      (node (ref "DD1") (pin "A15") (pinfunction "PA13_A15") (pintype "bidirectional"))
      (node (ref "X2") (pin "2") (pinfunction "2_2") (pintype "passive"))
    )
    (net (code "90") (name "/PA14") (class "Default")
      (node (ref "DD1") (pin "A14") (pinfunction "PA14_A14") (pintype "bidirectional"))
      (node (ref "X2") (pin "3") (pinfunction "3_3") (pintype "passive"))
    )
    (net (code "91") (name "/PA15") (class "Default")
      (node (ref "DD1") (pin "A13") (pinfunction "PA15_A13") (pintype "bidirectional"))
    )
    (net (code "92") (name "/PB0") (class "Default")
      (node (ref "DD1") (pin "R5") (pinfunction "PB0_R5") (pintype "bidirectional"))
    )
    (net (code "93") (name "/PB1") (class "Default")
      (node (ref "DD1") (pin "R4") (pinfunction "PB1_R4") (pintype "bidirectional"))
    )
    (net (code "94") (name "/PB2") (class "Default")
      (node (ref "DD1") (pin "M5") (pinfunction "PB2_M5") (pintype "bidirectional"))
    )
    (net (code "95") (name "/PB3") (class "Default")
      (node (ref "DD1") (pin "A10") (pinfunction "PB3_A10") (pintype "bidirectional"))
    )
    (net (code "96") (name "/PB4") (class "Default")
      (node (ref "DD1") (pin "A9") (pinfunction "PB4_A9") (pintype "bidirectional"))
    )
    (net (code "97") (name "/PB5") (class "Default")
      (node (ref "DD1") (pin "A8") (pinfunction "PB5_A8") (pintype "bidirectional"))
    )
    (net (code "98") (name "/PB6") (class "Default")
      (node (ref "DD1") (pin "B6") (pinfunction "PB6_B6") (pintype "bidirectional"))
    )
    (net (code "99") (name "/PB7") (class "Default")
      (node (ref "DD1") (pin "B5") (pinfunction "PB7_B5") (pintype "bidirectional"))
    )
    (net (code "100") (name "/PB8") (class "Default")
      (node (ref "DD1") (pin "A7") (pinfunction "PB8_A7") (pintype "bidirectional"))
    )
    (net (code "101") (name "/PB9") (class "Default")
      (node (ref "DD1") (pin "B4") (pinfunction "PB9_B4") (pintype "bidirectional"))
    )
    (net (code "102") (name "/PB10") (class "Default")
      (node (ref "DD1") (pin "P12") (pinfunction "PB10_P12") (pintype "bidirectional"))
    )
    (net (code "103") (name "/PB11") (class "Default")
      (node (ref "DD1") (pin "R13") (pinfunction "PB11_R13") (pintype "bidirectional"))
    )
    (net (code "104") (name "/PB12") (class "Default")
      (node (ref "DD1") (pin "L13") (pinfunction "PB12_L13") (pintype "bidirectional"))
    )
    (net (code "105") (name "/PB13") (class "Default")
      (node (ref "DD1") (pin "K14") (pinfunction "PB13_K14") (pintype "bidirectional"))
    )
    (net (code "106") (name "/PB14") (class "Default")
      (node (ref "DD1") (pin "R14") (pinfunction "PB14_R14") (pintype "bidirectional"))
    )
    (net (code "107") (name "/PB15") (class "Default")
      (node (ref "DD1") (pin "R15") (pinfunction "PB15_R15") (pintype "bidirectional"))
    )
    (net (code "108") (name "/PC0") (class "Default")
      (node (ref "DD1") (pin "M2") (pinfunction "PC0_M2") (pintype "bidirectional"))
    )
    (net (code "109") (name "/PC1") (class "Default")
      (node (ref "DD1") (pin "M3") (pinfunction "PC1_M3") (pintype "bidirectional"))
    )
    (net (code "110") (name "/PC2") (class "Default")
      (node (ref "DD1") (pin "M4") (pinfunction "PC2_M4") (pintype "bidirectional"))
    )
    (net (code "111") (name "/PC3") (class "Default")
      (node (ref "DD1") (pin "L4") (pinfunction "PC3_L4") (pintype "bidirectional"))
    )
    (net (code "112") (name "/PC4") (class "Default")
      (node (ref "DD1") (pin "N5") (pinfunction "PC4_N5") (pintype "bidirectional"))
    )
    (net (code "113") (name "/PC5") (class "Default")
      (node (ref "DD1") (pin "P5") (pinfunction "PC5_P5") (pintype "bidirectional"))
    )
    (net (code "114") (name "/PC6") (class "Default")
      (node (ref "DD1") (pin "H15") (pinfunction "PC6_H15") (pintype "bidirectional"))
    )
    (net (code "115") (name "/PC7") (class "Default")
      (node (ref "DD1") (pin "G15") (pinfunction "PC7_G15") (pintype "bidirectional"))
    )
    (net (code "116") (name "/PC12") (class "Default")
      (node (ref "DD1") (pin "A12") (pinfunction "PC12_A12") (pintype "bidirectional"))
    )
    (net (code "117") (name "/PC13") (class "Default")
      (node (ref "DD1") (pin "D1") (pinfunction "PC13_D1") (pintype "bidirectional"))
    )
    (net (code "118") (name "/PC14") (class "Default")
      (node (ref "C1") (pin "1") (pinfunction "1_1") (pintype "passive"))
      (node (ref "DD1") (pin "E1") (pinfunction "PC14_E1") (pintype "bidirectional"))
      (node (ref "Z2") (pin "1") (pinfunction "1_1") (pintype "passive"))
    )
    (net (code "119") (name "/PC15") (class "Default")
      (node (ref "C2") (pin "1") (pinfunction "1_1") (pintype "passive"))
      (node (ref "DD1") (pin "F1") (pinfunction "PC15_F1") (pintype "bidirectional"))
      (node (ref "Z2") (pin "2") (pinfunction "2_2") (pintype "passive"))
    )
    (net (code "120") (name "/PD2") (class "Default")
      (node (ref "DD1") (pin "D12") (pinfunction "PD2_D12") (pintype "bidirectional"))
    )
    (net (code "121") (name "/PD3") (class "Default")
      (node (ref "DD1") (pin "C11") (pinfunction "PD3_C11") (pintype "bidirectional"))
    )
    (net (code "122") (name "/PD4") (class "Default")
      (node (ref "DD1") (pin "D11") (pinfunction "PD4_D11") (pintype "bidirectional"))
    )
    (net (code "123") (name "/PD5") (class "Default")
      (node (ref "DD1") (pin "C10") (pinfunction "PD5_C10") (pintype "bidirectional"))
    )
    (net (code "124") (name "/PD6") (class "Default")
      (node (ref "DD1") (pin "B11") (pinfunction "PD6_B11") (pintype "bidirectional"))
    )
    (net (code "125") (name "/PD7") (class "Default")
      (node (ref "DD1") (pin "A11") (pinfunction "PD7_A11") (pintype "bidirectional"))
    )
    (net (code "126") (name "/PD11") (class "Default")
      (node (ref "DD1") (pin "N10") (pinfunction "PD11_N10") (pintype "bidirectional"))
    )
    (net (code "127") (name "/PD12") (class "Default")
      (node (ref "DD1") (pin "M10") (pinfunction "PD12_M10") (pintype "bidirectional"))
    )
    (net (code "128") (name "/PD13") (class "Default")
      (node (ref "DD1") (pin "M11") (pinfunction "PD13_M11") (pintype "bidirectional"))
    )
    (net (code "129") (name "/PE2") (class "Default")
      (node (ref "DD1") (pin "A3") (pinfunction "PE2_A3") (pintype "bidirectional"))
    )
    (net (code "130") (name "/PE3") (class "Default")
      (node (ref "DD1") (pin "A2") (pinfunction "PE3_A2") (pintype "bidirectional"))
    )
    (net (code "131") (name "/PE5") (class "Default")
      (node (ref "DD1") (pin "B1") (pinfunction "PE5_B1") (pintype "bidirectional"))
    )
    (net (code "132") (name "/PE6") (class "Default")
      (node (ref "DD1") (pin "B2") (pinfunction "PE6_B2") (pintype "bidirectional"))
    )
    (net (code "133") (name "/PF6") (class "Default")
      (node (ref "DD1") (pin "K2") (pinfunction "PF6_K2") (pintype "bidirectional"))
    )
    (net (code "134") (name "/PF7") (class "Default")
      (node (ref "DD1") (pin "K1") (pinfunction "PF7_K1") (pintype "bidirectional"))
    )
    (net (code "135") (name "/PF8") (class "Default")
      (node (ref "DD1") (pin "L3") (pinfunction "PF8_L3") (pintype "bidirectional"))
    )
    (net (code "136") (name "/PF9") (class "Default")
      (node (ref "DD1") (pin "L2") (pinfunction "PF9_L2") (pintype "bidirectional"))
    )
    (net (code "137") (name "/PF10") (class "Default")
      (node (ref "DD1") (pin "L1") (pinfunction "PF10_L1") (pintype "bidirectional"))
    )
    (net (code "138") (name "/PF11") (class "Default")
      (node (ref "DD1") (pin "P8") (pinfunction "PF11_P8") (pintype "bidirectional"))
    )
    (net (code "139") (name "/PG2") (class "Default")
      (node (ref "DD1") (pin "M13") (pinfunction "PG2_M13") (pintype "bidirectional"))
    )
    (net (code "140") (name "/PG3") (class "Default")
      (node (ref "DD1") (pin "M12") (pinfunction "PG3_M12") (pintype "bidirectional"))
    )
    (net (code "141") (name "/PG6") (class "Default")
      (node (ref "DD1") (pin "J15") (pinfunction "PG6_J15") (pintype "bidirectional"))
    )
    (net (code "142") (name "/PG7") (class "Default")
      (node (ref "DD1") (pin "J14") (pinfunction "PG7_J14") (pintype "bidirectional"))
    )
    (net (code "143") (name "/PG8") (class "Default")
      (node (ref "DD1") (pin "H14") (pinfunction "PG8_H14") (pintype "bidirectional"))
    )
    (net (code "144") (name "/PG9") (class "Default")
      (node (ref "DD1") (pin "D9") (pinfunction "PG9_D9") (pintype "bidirectional"))
    )
    (net (code "145") (name "/PG10") (class "Default")
      (node (ref "DD1") (pin "C8") (pinfunction "PG10_C8") (pintype "bidirectional"))
    )
    (net (code "146") (name "/PG11") (class "Default")
      (node (ref "DD1") (pin "B8") (pinfunction "PG11_B8") (pintype "bidirectional"))
    )
    (net (code "147") (name "/PG13") (class "Default")
      (node (ref "DD1") (pin "B3") (pinfunction "PG13_B3") (pintype "bidirectional"))
    )
    (net (code "148") (name "/PG14") (class "Default")
      (node (ref "DD1") (pin "A4") (pinfunction "PG14_A4") (pintype "bidirectional"))
    )
    (net (code "149") (name "/PG15") (class "Default")
      (node (ref "DD1") (pin "B7") (pinfunction "PG15_B7") (pintype "bidirectional"))
    )
    (net (code "150") (name "/PH0") (class "Default")
      (node (ref "C14") (pin "1") (pinfunction "1_1") (pintype "passive"))
      (node (ref "DD1") (pin "G1") (pinfunction "PH0_G1") (pintype "bidirectional"))
      (node (ref "Z1") (pin "1") (pinfunction "1_1") (pintype "passive"))
    )
    (net (code "151") (name "/PH1") (class "Default")
      (node (ref "C15") (pin "1") (pinfunction "1_1") (pintype "passive"))
      (node (ref "DD1") (pin "H1") (pinfunction "PH1_H1") (pintype "bidirectional"))
      (node (ref "Z1") (pin "3") (pinfunction "3_3") (pintype "passive"))
    )
    (net (code "152") (name "/PH2") (class "Default")
      (node (ref "DD1") (pin "K4") (pinfunction "PH2_K4") (pintype "bidirectional"))
    )
    (net (code "153") (name "/PH3") (class "Default")
      (node (ref "DD1") (pin "J4") (pinfunction "PH3_J4") (pintype "bidirectional"))
    )
    (net (code "154") (name "/PH4") (class "Default")
      (node (ref "DD1") (pin "H4") (pinfunction "PH4_H4") (pintype "bidirectional"))
    )
    (net (code "155") (name "/PH5") (class "Default")
      (node (ref "DD1") (pin "J3") (pinfunction "PH5_J3") (pintype "bidirectional"))
    )
    (net (code "156") (name "/PH6") (class "Default")
      (node (ref "DD1") (pin "P13") (pinfunction "PH6_P13") (pintype "bidirectional"))
    )
    (net (code "157") (name "/PH7") (class "Default")
      (node (ref "DD1") (pin "N13") (pinfunction "PH7_N13") (pintype "bidirectional"))
    )
    (net (code "158") (name "/PH8") (class "Default")
      (node (ref "DD1") (pin "P14") (pinfunction "PH8_P14") (pintype "bidirectional"))
    )
    (net (code "159") (name "/PH9") (class "Default")
      (node (ref "DD1") (pin "N14") (pinfunction "PH9_N14") (pintype "bidirectional"))
    )
    (net (code "160") (name "/PH10") (class "Default")
      (node (ref "DD1") (pin "P15") (pinfunction "PH10_P15") (pintype "bidirectional"))
    )
    (net (code "161") (name "/PH11") (class "Default")
      (node (ref "DD1") (pin "N15") (pinfunction "PH11_N15") (pintype "bidirectional"))
    )
    (net (code "162") (name "/PH12") (class "Default")
      (node (ref "DD1") (pin "M15") (pinfunction "PH12_M15") (pintype "bidirectional"))
    )
    (net (code "163") (name "/PH13") (class "Default")
      (node (ref "DD1") (pin "E12") (pinfunction "PH13_E12") (pintype "bidirectional"))
    )
    (net (code "164") (name "/PH14") (class "Default")
      (node (ref "DD1") (pin "E13") (pinfunction "PH14_E13") (pintype "bidirectional"))
    )
    (net (code "165") (name "/PH15") (class "Default")
      (node (ref "DD1") (pin "D13") (pinfunction "PH15_D13") (pintype "bidirectional"))
    )
    (net (code "166") (name "/PI0") (class "Default")
      (node (ref "DD1") (pin "E14") (pinfunction "PI0_E14") (pintype "bidirectional"))
    )
    (net (code "167") (name "/PI1") (class "Default")
      (node (ref "DD1") (pin "D14") (pinfunction "PI1_D14") (pintype "bidirectional"))
    )
    (net (code "168") (name "/PI2") (class "Default")
      (node (ref "DD1") (pin "C14") (pinfunction "PI2_C14") (pintype "bidirectional"))
    )
    (net (code "169") (name "/PI3") (class "Default")
      (node (ref "DD1") (pin "C13") (pinfunction "PI3_C13") (pintype "bidirectional"))
    )
    (net (code "170") (name "/PI4") (class "Default")
      (node (ref "DD1") (pin "C3") (pinfunction "PI4_C3") (pintype "bidirectional"))
    )
    (net (code "171") (name "/PI5") (class "Default")
      (node (ref "DD1") (pin "D3") (pinfunction "PI5_D3") (pintype "bidirectional"))
    )
    (net (code "172") (name "/PI6") (class "Default")
      (node (ref "DD1") (pin "D6") (pinfunction "PI6_D6") (pintype "bidirectional"))
    )
    (net (code "173") (name "/PI7") (class "Default")
      (node (ref "DD1") (pin "D4") (pinfunction "PI7_D4") (pintype "bidirectional"))
    )
    (net (code "174") (name "/PI8") (class "Default")
      (node (ref "DD1") (pin "C2") (pinfunction "PI8_C2") (pintype "bidirectional"))
    )
    (net (code "175") (name "/PI9") (class "Default")
      (node (ref "DD1") (pin "E4") (pinfunction "PI9_E4") (pintype "bidirectional"))
    )
    (net (code "176") (name "/PI10") (class "Default")
      (node (ref "DD1") (pin "D5") (pinfunction "PI10_D5") (pintype "bidirectional"))
    )
    (net (code "177") (name "/PI11") (class "Default")
      (node (ref "DD1") (pin "F3") (pinfunction "PI11_F3") (pintype "bidirectional"))
    )
    (net (code "178") (name "/PI12") (class "Default")
      (node (ref "DD1") (pin "E3") (pinfunction "PI12_E3") (pintype "bidirectional"))
    )
    (net (code "179") (name "/PI13") (class "Default")
      (node (ref "DD1") (pin "G3") (pinfunction "PI13_G3") (pintype "bidirectional"))
    )
    (net (code "180") (name "/PI14") (class "Default")
      (node (ref "DD1") (pin "H3") (pinfunction "PI14_H3") (pintype "bidirectional"))
    )
    (net (code "181") (name "/PJ12") (class "Default")
      (node (ref "DD1") (pin "B10") (pinfunction "PJ12_B10") (pintype "bidirectional"))
    )
    (net (code "182") (name "/PK3") (class "Default")
      (node (ref "DD1") (pin "D8") (pinfunction "PK3_D8") (pintype "bidirectional"))
    )
    (net (code "183") (name "/PK7") (class "Default")
      (node (ref "DD1") (pin "C4") (pinfunction "PK7_C4") (pintype "bidirectional"))
    )
    (net (code "185") (name "/SDMMC_D0") (class "Default")
      (node (ref "DD1") (pin "G14") (pinfunction "PC8_G14") (pintype "bidirectional"))
    )
    (net (code "186") (name "/SDMMC_D1") (class "Default")
      (node (ref "DD1") (pin "F14") (pinfunction "PC9_F14") (pintype "bidirectional"))
    )
    (net (code "187") (name "/SDMMC_D2") (class "Default")
      (node (ref "DD1") (pin "B14") (pinfunction "PC10_B14") (pintype "bidirectional"))
    )
    (net (code "188") (name "/SDMMC_D3") (class "Default")
      (node (ref "DD1") (pin "B13") (pinfunction "PC11_B13") (pintype "bidirectional"))
    )
    (net (code "190") (name "/USB_FS_N") (class "Default")
      (node (ref "DD1") (pin "C15") (pinfunction "PA11_C15") (pintype "bidirectional"))
    )
    (net (code "191") (name "/USB_FS_P") (class "Default")
      (node (ref "DD1") (pin "B15") (pinfunction "PA12_B15") (pintype "bidirectional"))
    )
    (net (code "192") (name "/nRST") (class "Default")
      (node (ref "C16") (pin "1") (pinfunction "1_1") (pintype "passive"))
      (node (ref "DD1") (pin "J1") (pinfunction "NRST_J1") (pintype "bidirectional"))
      (node (ref "R8") (pin "2") (pinfunction "2_2") (pintype "passive"))
      (node (ref "X2") (pin "5") (pinfunction "5_5") (pintype "passive"))
    )
    (net (code "201") (name "GND") (class "Default")
      (node (ref "C1") (pin "2") (pinfunction "2_2") (pintype "passive"))
      (node (ref "C12") (pin "2") (pinfunction "2_2") (pintype "passive"))
      (node (ref "C13") (pin "2") (pinfunction "2_2") (pintype "passive"))
      (node (ref "C14") (pin "2") (pinfunction "2_2") (pintype "passive"))
      (node (ref "C15") (pin "2") (pinfunction "2_2") (pintype "passive"))
      (node (ref "C16") (pin "2") (pinfunction "2_2") (pintype "passive"))
      (node (ref "C17") (pin "2") (pinfunction "2_2") (pintype "passive"))
      (node (ref "C18") (pin "2") (pinfunction "2_2") (pintype "passive"))
      (node (ref "C19") (pin "2") (pinfunction "2_2") (pintype "passive"))
      (node (ref "C2") (pin "2") (pinfunction "2_2") (pintype "passive"))
      (node (ref "C20") (pin "2") (pinfunction "2_2") (pintype "passive"))
      (node (ref "C21") (pin "2") (pinfunction "2_2") (pintype "passive"))
      (node (ref "C22") (pin "2") (pinfunction "2_2") (pintype "passive"))
      (node (ref "C23") (pin "2") (pinfunction "2_2") (pintype "passive"))
      (node (ref "C24") (pin "2") (pinfunction "2_2") (pintype "passive"))
      (node (ref "C25") (pin "2") (pinfunction "2_2") (pintype "passive"))
      (node (ref "C26") (pin "2") (pinfunction "2_2") (pintype "passive"))
      (node (ref "C27") (pin "2") (pinfunction "2_2") (pintype "passive"))
      (node (ref "C28") (pin "2") (pinfunction "2_2") (pintype "passive"))
      (node (ref "C29") (pin "2") (pinfunction "2_2") (pintype "passive"))
      (node (ref "C30") (pin "2") (pinfunction "2_2") (pintype "passive"))
      (node (ref "C31") (pin "2") (pinfunction "2_2") (pintype "passive"))
      (node (ref "C32") (pin "2") (pinfunction "2_2") (pintype "passive"))
      (node (ref "C73") (pin "2") (pinfunction "2_2") (pintype "passive"))
      (node (ref "C74") (pin "2") (pinfunction "2_2") (pintype "passive"))
      (node (ref "C75") (pin "2") (pinfunction "2_2") (pintype "passive"))
      (node (ref "C76") (pin "2") (pinfunction "2_2") (pintype "passive"))
      (node (ref "C84") (pin "2") (pinfunction "2_2") (pintype "passive"))
      (node (ref "C85") (pin "2") (pinfunction "2_2") (pintype "passive"))
      (node (ref "C86") (pin "2") (pinfunction "2_2") (pintype "passive"))
      (node (ref "DD1") (pin "F10") (pinfunction "VSS_F10") (pintype "power_in"))
      (node (ref "DD1") (pin "F2") (pinfunction "VSS_F2") (pintype "power_in"))
      (node (ref "DD1") (pin "F6") (pinfunction "VSS_F6") (pintype "power_in"))
      (node (ref "DD1") (pin "F7") (pinfunction "VSS_F7") (pintype "power_in"))
      (node (ref "DD1") (pin "F8") (pinfunction "VSS_F8") (pintype "power_in"))
      (node (ref "DD1") (pin "F9") (pinfunction "VSS_F9") (pintype "power_in"))
      (node (ref "DD1") (pin "G10") (pinfunction "VSS_G10") (pintype "power_in"))
      (node (ref "DD1") (pin "G6") (pinfunction "VSS_G6") (pintype "power_in"))
      (node (ref "DD1") (pin "H10") (pinfunction "VSS_H10") (pintype "power_in"))
      (node (ref "DD1") (pin "H6") (pinfunction "VSS_H6") (pintype "power_in"))
      (node (ref "DD1") (pin "J10") (pinfunction "VSS_J10") (pintype "power_in"))
      (node (ref "DD1") (pin "J6") (pinfunction "VSS_J6") (pintype "power_in"))
      (node (ref "DD1") (pin "K10") (pinfunction "VSS_K10") (pintype "power_in"))
      (node (ref "DD1") (pin "K6") (pinfunction "VSS_K6") (pintype "power_in"))
      (node (ref "DD1") (pin "K7") (pinfunction "VSS_K7") (pintype "power_in"))
      (node (ref "DD1") (pin "K8") (pinfunction "VSS_K8") (pintype "power_in"))
      (node (ref "DD1") (pin "K9") (pinfunction "VSS_K9") (pintype "power_in"))
      (node (ref "DD1") (pin "L6") (pinfunction "VSS_L6") (pintype "power_in"))
      (node (ref "DD1") (pin "M1") (pinfunction "VSSA_M1") (pintype "power_in"))
      (node (ref "DD1") (pin "N1") (pinfunction "VREF-_N1") (pintype "power_in"))
      (node (ref "R2") (pin "2") (pinfunction "2_2") (pintype "passive"))
      (node (ref "R4") (pin "2") (pinfunction "2_2") (pintype "passive"))
      (node (ref "R5") (pin "1") (pinfunction "1_1") (pintype "passive"))
      (node (ref "X2") (pin "0") (pinfunction "Bind_0") (pintype "passive"))
      (node (ref "X2") (pin "4") (pinfunction "4_4") (pintype "passive"))
      (node (ref "Z1") (pin "2") (pinfunction "2_2") (pintype "passive"))
      (node (ref "Z1") (pin "4") (pinfunction "4_4") (pintype "passive"))
    )
    (net (code "202") (name "Net-(DD1B-BOOT)") (class "Default")
      (node (ref "DD1") (pin "E6") (pinfunction "BOOT_E6") (pintype "input"))
      (node (ref "R1") (pin "1") (pinfunction "1_1") (pintype "passive"))
      (node (ref "R2") (pin "1") (pinfunction "1_1") (pintype "passive"))
    )
    (net (code "203") (name "Net-(DD1B-PDR_ON)") (class "Default")
      (node (ref "DD1") (pin "E5") (pinfunction "PDR_ON_E5") (pintype "input"))
      (node (ref "R3") (pin "1") (pinfunction "1_1") (pintype "passive"))
      (node (ref "R4") (pin "1") (pinfunction "1_1") (pintype "passive"))
    )
    (net (code "204") (name "Net-(DD1C-BYPASS)") (class "Default")
      (node (ref "DD1") (pin "L5") (pinfunction "BYPASS_L5") (pintype "input"))
      (node (ref "R5") (pin "2") (pinfunction "2_2") (pintype "passive"))
    )
    (net (code "205") (name "Net-(DD1C-VCAP_1)") (class "Default")
      (node (ref "C32") (pin "1") (pinfunction "1_1") (pintype "passive"))
      (node (ref "DD1") (pin "L11") (pinfunction "VCAP_1_L11") (pintype "power_in"))
    )
    (net (code "206") (name "Net-(DD1C-VCAP_2)") (class "Default")
      (node (ref "C31") (pin "1") (pinfunction "1_1") (pintype "passive"))
      (node (ref "DD1") (pin "E11") (pinfunction "VCAP_2_E11") (pintype "power_in"))
    )
    (net (code "207") (name "unconnected-(X2-Pad6)") (class "Default")
      (node (ref "X2") (pin "6") (pinfunction "6_6") (pintype "passive"))
    )
  )
)
